# design.net
KiCad netlist of a schematic drawn in Altium Designer
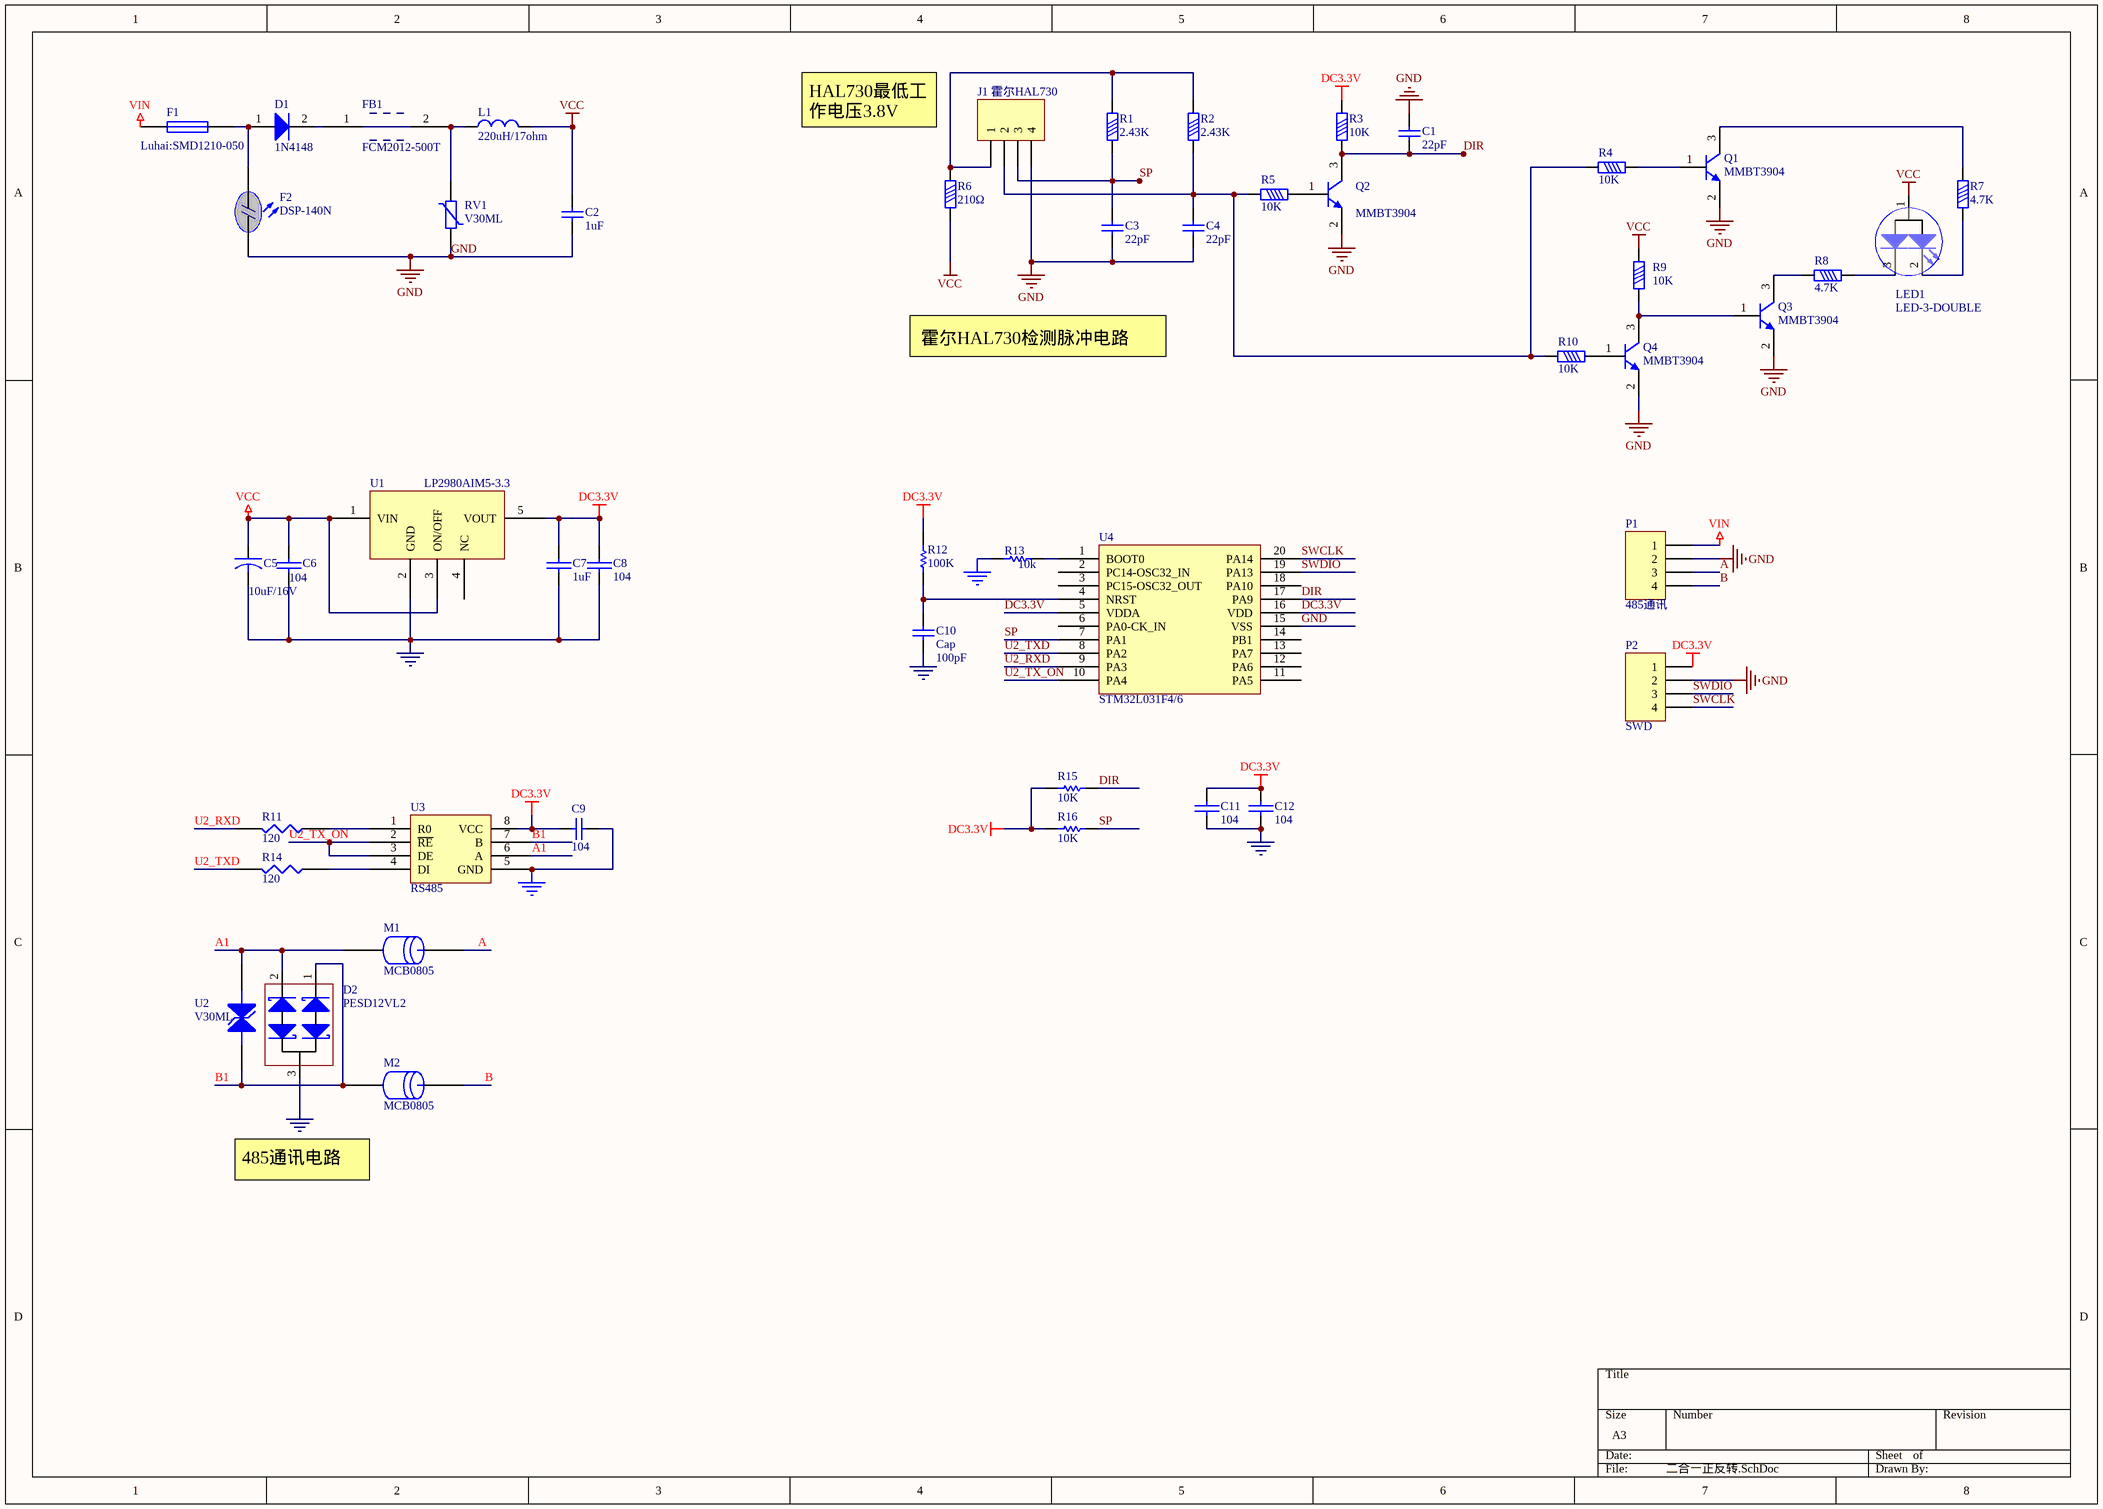
[diagram p0: 二合一正反转.SchDoc]

(export (version "E")
  (design (tool "Eeschema 10.0.6"))
  (components
    (comp (ref "C1")
      (value "22pF")
      (footprint "0603C")
      (description "Polarized Capacitor (Radial)")
      (fields (field (name "Comment") "Cap Chip 0603") (field (name "PUBLISHER") "Altium Limited"))
      (libsource (lib "EButterflyIntegratedLibrary") (part "Cap Chip 0603"))
    )
    (comp (ref "C2")
      (value "1uF")
      (footprint "0805C")
      (description "Polarized Capacitor (Radial)")
      (fields (field (name "PUBLISHER") "Altium Limited"))
      (libsource (lib "EButterflyIntegratedLibrary") (part "Cap Chip 0805"))
    )
    (comp (ref "C3")
      (value "22pF")
      (footprint "0603C")
      (description "Polarized Capacitor (Radial)")
      (fields (field (name "Comment") "Cap Chip 0603") (field (name "PUBLISHER") "Altium Limited"))
      (libsource (lib "EButterflyIntegratedLibrary") (part "Cap Chip 0603"))
    )
    (comp (ref "C4")
      (value "22pF")
      (footprint "0603C")
      (description "Polarized Capacitor (Radial)")
      (fields (field (name "Comment") "Cap Chip 0603") (field (name "PUBLISHER") "Altium Limited"))
      (libsource (lib "EButterflyIntegratedLibrary") (part "Cap Chip 0603"))
    )
    (comp (ref "C5")
      (value "10uF/16V")
      (footprint "A3216")
      (description "Capacitor")
      (libsource (lib "*") (part "CAPACITOR"))
    )
    (comp (ref "C6")
      (value "104")
      (footprint "0603C")
      (description "Capacitor")
      (libsource (lib "*") (part "CAP"))
    )
    (comp (ref "C7")
      (value "1uF")
      (footprint "0603C")
      (description "Capacitor")
      (libsource (lib "*") (part "CAP"))
    )
    (comp (ref "C8")
      (value "104")
      (footprint "0603C")
      (description "Capacitor")
      (libsource (lib "*") (part "CAP"))
    )
    (comp (ref "C9")
      (value "104")
      (footprint "0603C")
      (description "Capacitor")
      (fields (field (name "PUBLISHER") "*"))
      (libsource (lib "*") (part "Cap"))
    )
    (comp (ref "C10")
      (value "Cap")
      (footprint "0603C")
      (description "Capacitor")
      (fields (field (name "ALTIUM_VALUE") "100pF") (field (name "PUBLISHER") "Altium Limited"))
      (libsource (lib "Miscellaneous Devices") (part "Cap"))
    )
    (comp (ref "C11")
      (value "104")
      (footprint "0603C")
      (description "Capacitor")
      (libsource (lib "*") (part "CAP"))
    )
    (comp (ref "C12")
      (value "104")
      (footprint "0603C")
      (description "Capacitor")
      (libsource (lib "*") (part "CAP"))
    )
    (comp (ref "D1")
      (value "1N4148")
      (footprint "1N4148")
      (libsource (lib "Integrated_Library1") (part "1N4148"))
    )
    (comp (ref "D2") (value "PESD12VL2") (footprint "SOT23") (libsource (lib "lewis lib") (part "TVS")))
    (comp (ref "F1")
      (value "Luhai:SMD1210-050")
      (footprint "1210R")
      (description "Fuse")
      (fields (field (name "PUBLISHER") "Altium Limited"))
      (libsource (lib "Miscellaneous Devices") (part "Fuse 1"))
    )
    (comp (ref "F2")
      (value "DSP-140N")
      (footprint "DSP")
      (libsource (lib "Integrated_Library1") (part "DSP-140N"))
    )
    (comp (ref "FB1")
      (value "FCM2012-500T")
      (footprint "FB")
      (libsource (lib "Integrated_Library1") (part "FCM2012-500T"))
    )
    (comp (ref "J1")
      (value "霍尔HAL730")
      (footprint "HDR1X4")
      (description "Header, 4-Pin")
      (fields (field (name "PUBLISHER") "Altium Limited"))
      (libsource (lib "EButterflyIntegratedLibrary") (part "Header 4"))
    )
    (comp (ref "L1")
      (value "220uH/17ohm")
      (footprint "220uH/17ohm")
      (libsource (lib "Integrated_Library1") (part "220uH/17ohm"))
    )
    (comp (ref "LED1")
      (value "LED-3-DOUBLE")
      (footprint "LED-R3-H5-DOUBLE")
      (libsource (lib "Integrated_Library1") (part "DOUB-LED"))
    )
    (comp (ref "M1")
      (value "MCB0805")
      (footprint "0805F")
      (description "magnetic bead")
      (libsource (lib "lewis lib") (part "MAGNETIC BEAD"))
    )
    (comp (ref "M2")
      (value "MCB0805")
      (footprint "0805F")
      (description "magnetic bead")
      (libsource (lib "lewis lib") (part "MAGNETIC BEAD"))
    )
    (comp (ref "P1")
      (value "485通讯")
      (footprint "HDR1X4")
      (description "Header, 4-Pin, Right Angle")
      (fields (field (name "PUBLISHER") "Altium Limited"))
      (libsource (lib "Miscellaneous Connectors") (part "Header 4H"))
    )
    (comp (ref "P2")
      (value "SWD")
      (footprint "MHDR1X4")
      (description "Header, 4-Pin")
      (fields (field (name "PUBLISHER") "Altium Limited"))
      (libsource (lib "Miscellaneous Connectors") (part "Header 4"))
    )
    (comp (ref "Q1")
      (value "MMBT3904")
      (footprint "MMBT3904")
      (libsource (lib "Integrated_Library1") (part "MMBT3904"))
    )
    (comp (ref "Q2")
      (value "MMBT3904")
      (footprint "MMBT3904")
      (libsource (lib "Integrated_Library1") (part "MMBT3904"))
    )
    (comp (ref "Q3")
      (value "MMBT3904")
      (footprint "MMBT3904")
      (libsource (lib "Integrated_Library1") (part "MMBT3904"))
    )
    (comp (ref "Q4")
      (value "MMBT3904")
      (footprint "MMBT3904")
      (libsource (lib "Integrated_Library1") (part "MMBT3904"))
    )
    (comp (ref "R1")
      (value "2.43K")
      (footprint "0603C")
      (description "Resistor")
      (fields (field (name "Comment") "Resistor Chip 0603") (field (name "PUBLISHER") "Altium Limited"))
      (libsource (lib "") (part "Resistor Chip 0603_2"))
    )
    (comp (ref "R2")
      (value "2.43K")
      (footprint "0603C")
      (description "Resistor")
      (fields (field (name "Comment") "Resistor Chip 0603") (field (name "PUBLISHER") "Altium Limited"))
      (libsource (lib "") (part "Resistor Chip 0603_2"))
    )
    (comp (ref "R3")
      (value "10K")
      (footprint "0603C")
      (description "Resistor")
      (fields (field (name "Comment") "Resistor Chip 0603") (field (name "PUBLISHER") "Altium Limited"))
      (libsource (lib "") (part "Resistor Chip 0603_2"))
    )
    (comp (ref "R4")
      (value "10K")
      (footprint "0603C")
      (description "Resistor")
      (fields (field (name "Comment") "Resistor Chip 0603") (field (name "PUBLISHER") "Altium Limited"))
      (libsource (lib "") (part "Resistor Chip 0603_1"))
    )
    (comp (ref "R5")
      (value "10K")
      (footprint "0603C")
      (description "Resistor")
      (fields (field (name "Comment") "Resistor Chip 0603") (field (name "PUBLISHER") "Altium Limited"))
      (libsource (lib "") (part "Resistor Chip 0603_1"))
    )
    (comp (ref "R6")
      (value "210Ω")
      (footprint "0603C")
      (description "Resistor")
      (fields (field (name "Comment") "Resistor Chip 0603") (field (name "PUBLISHER") "Altium Limited"))
      (libsource (lib "EButterflyIntegratedLibrary") (part "Resistor Chip 0603"))
    )
    (comp (ref "R7")
      (value "4.7K")
      (footprint "0603C")
      (description "Resistor")
      (fields (field (name "Comment") "Resistor Chip 0603") (field (name "PUBLISHER") "Altium Limited"))
      (libsource (lib "EButterflyIntegratedLibrary") (part "Resistor Chip 0603"))
    )
    (comp (ref "R8")
      (value "4.7K")
      (footprint "0603C")
      (description "Resistor")
      (fields (field (name "Comment") "Resistor Chip 0603") (field (name "PUBLISHER") "Altium Limited"))
      (libsource (lib "") (part "Resistor Chip 0603_1"))
    )
    (comp (ref "R9")
      (value "10K")
      (footprint "0603C")
      (description "Resistor")
      (fields (field (name "Comment") "Resistor Chip 0603") (field (name "PUBLISHER") "Altium Limited"))
      (libsource (lib "EButterflyIntegratedLibrary") (part "Resistor Chip 0603"))
    )
    (comp (ref "R10")
      (value "10K")
      (footprint "0603C")
      (description "Resistor")
      (fields (field (name "Comment") "Resistor Chip 0603") (field (name "PUBLISHER") "Altium Limited"))
      (libsource (lib "") (part "Resistor Chip 0603_1"))
    )
    (comp (ref "R11") (value "120") (footprint "0603R") (libsource (lib "*") (part "RES1")))
    (comp (ref "R12")
      (value "100K")
      (footprint "0603R")
      (description "Resistor")
      (fields (field (name "PUBLISHER") "Altium Limited"))
      (libsource (lib "Miscellaneous Devices") (part "Res1"))
    )
    (comp (ref "R13")
      (value "10k")
      (footprint "0603R")
      (description "Resistor")
      (fields (field (name "PUBLISHER") "Altium Limited"))
      (libsource (lib "Miscellaneous Devices") (part "Res1"))
    )
    (comp (ref "R14") (value "120") (footprint "0603R") (libsource (lib "*") (part "RES1")))
    (comp (ref "R15")
      (value "10K")
      (footprint "0603R")
      (description "Resistor")
      (fields (field (name "PUBLISHER") "Altium Limited"))
      (libsource (lib "Miscellaneous Devices") (part "Res1"))
    )
    (comp (ref "R16")
      (value "10K")
      (footprint "0603R")
      (description "Resistor")
      (fields (field (name "PUBLISHER") "Altium Limited"))
      (libsource (lib "Miscellaneous Devices") (part "Res1"))
    )
    (comp (ref "RV1") (value "V30ML") (footprint "RV") (libsource (lib "Integrated_Library1") (part "V30ML")))
    (comp (ref "U1")
      (value "LP2980AIM5-3.3")
      (footprint "SOT-23-5")
      (libsource (lib "lewis lib") (part "LP2980AIM5-3.3"))
    )
    (comp (ref "U2") (value "V30ML") (footprint "0805C-E") (libsource (lib "*") (part "V30ML")))
    (comp (ref "U3") (value "RS485") (footprint "SOP8") (libsource (lib "*") (part "RS485")))
    (comp (ref "U4")
      (value "STM32L031F4/6")
      (footprint "TSSOP20")
      (libsource (lib "lewis lib") (part "STM32L031F4/6"))
    )
  )
  (nets
    (net (code "1") (name "/A") (class "Default")
      (node (ref "M1") (pin "2") (pintype "passive"))
      (node (ref "P1") (pin "3") (pinfunction "3_3") (pintype "passive"))
    )
    (net (code "2") (name "/A1") (class "Default")
      (node (ref "D2") (pin "2") (pinfunction "2_2") (pintype "passive"))
      (node (ref "M1") (pin "1") (pintype "passive"))
      (node (ref "U2") (pin "2") (pinfunction "2_2") (pintype "passive"))
      (node (ref "U3") (pin "6") (pinfunction "A_6") (pintype "passive"))
    )
    (net (code "3") (name "/B") (class "Default")
      (node (ref "M2") (pin "2") (pintype "passive"))
      (node (ref "P1") (pin "4") (pinfunction "4_4") (pintype "passive"))
    )
    (net (code "4") (name "/B1") (class "Default")
      (node (ref "D2") (pin "1") (pinfunction "1_1") (pintype "passive"))
      (node (ref "M2") (pin "1") (pintype "passive"))
      (node (ref "U2") (pin "1") (pinfunction "1_1") (pintype "passive"))
      (node (ref "U3") (pin "7") (pinfunction "B_7") (pintype "passive"))
    )
    (net (code "5") (name "/DIR") (class "Default")
      (node (ref "C1") (pin "1") (pinfunction "1_1") (pintype "passive"))
      (node (ref "Q2") (pin "3") (pinfunction "C_3") (pintype "passive"))
      (node (ref "R15") (pin "1") (pinfunction "1_1") (pintype "passive"))
      (node (ref "R3") (pin "1") (pinfunction "1_1") (pintype "passive"))
      (node (ref "U4") (pin "17") (pinfunction "PA9_17") (pintype "passive"))
    )
    (net (code "6") (name "/SP") (class "Default")
      (node (ref "C3") (pin "2") (pinfunction "2_2") (pintype "passive"))
      (node (ref "J1") (pin "3") (pinfunction "3_3") (pintype "passive"))
      (node (ref "R1") (pin "1") (pinfunction "1_1") (pintype "passive"))
      (node (ref "R16") (pin "2") (pinfunction "2_2") (pintype "passive"))
      (node (ref "U4") (pin "7") (pinfunction "PA1_7") (pintype "passive"))
    )
    (net (code "7") (name "/SWCLK") (class "Default")
      (node (ref "P2") (pin "4") (pinfunction "4_4") (pintype "passive"))
      (node (ref "U4") (pin "20") (pinfunction "PA14_20") (pintype "passive"))
    )
    (net (code "8") (name "/SWDIO") (class "Default")
      (node (ref "P2") (pin "3") (pinfunction "3_3") (pintype "passive"))
      (node (ref "U4") (pin "19") (pinfunction "PA13_19") (pintype "passive"))
    )
    (net (code "9") (name "/U2_RXD") (class "Default")
      (node (ref "R11") (pin "2") (pinfunction "2_2") (pintype "passive"))
      (node (ref "U4") (pin "9") (pinfunction "PA3_9") (pintype "passive"))
    )
    (net (code "10") (name "/U2_TXD") (class "Default")
      (node (ref "R14") (pin "2") (pinfunction "2_2") (pintype "passive"))
      (node (ref "U4") (pin "8") (pinfunction "PA2_8") (pintype "passive"))
    )
    (net (code "11") (name "/U2_TX_ON") (class "Default")
      (node (ref "U3") (pin "2") (pinfunction "~{RE}_2") (pintype "passive"))
      (node (ref "U3") (pin "3") (pinfunction "DE_3") (pintype "passive"))
      (node (ref "U4") (pin "10") (pinfunction "PA4_10") (pintype "passive"))
    )
    (net (code "12") (name "DC3.3V") (class "Default")
      (node (ref "C11") (pin "1") (pinfunction "1_1") (pintype "passive"))
      (node (ref "C12") (pin "1") (pinfunction "1_1") (pintype "passive"))
      (node (ref "C7") (pin "1") (pinfunction "1_1") (pintype "passive"))
      (node (ref "C8") (pin "1") (pinfunction "1_1") (pintype "passive"))
      (node (ref "C9") (pin "1") (pinfunction "1_1") (pintype "passive"))
      (node (ref "P2") (pin "1") (pinfunction "1_1") (pintype "passive"))
      (node (ref "R12") (pin "1") (pinfunction "1_1") (pintype "passive"))
      (node (ref "R15") (pin "2") (pinfunction "2_2") (pintype "passive"))
      (node (ref "R16") (pin "1") (pinfunction "1_1") (pintype "passive"))
      (node (ref "R3") (pin "2") (pinfunction "2_2") (pintype "passive"))
      (node (ref "U1") (pin "5") (pinfunction "VOUT_5") (pintype "passive"))
      (node (ref "U3") (pin "8") (pinfunction "VCC_8") (pintype "passive"))
      (node (ref "U4") (pin "16") (pinfunction "VDD_16") (pintype "passive"))
      (node (ref "U4") (pin "5") (pinfunction "VDDA_5") (pintype "passive"))
    )
    (net (code "13") (name "GND") (class "Default")
      (node (ref "C1") (pin "2") (pinfunction "2_2") (pintype "passive"))
      (node (ref "C10") (pin "1") (pinfunction "1_1") (pintype "passive"))
      (node (ref "C11") (pin "2") (pinfunction "2_2") (pintype "passive"))
      (node (ref "C12") (pin "2") (pinfunction "2_2") (pintype "passive"))
      (node (ref "C2") (pin "1") (pinfunction "1_1") (pintype "passive"))
      (node (ref "C3") (pin "1") (pinfunction "1_1") (pintype "passive"))
      (node (ref "C4") (pin "1") (pinfunction "1_1") (pintype "passive"))
      (node (ref "C5") (pin "2") (pinfunction "2_2") (pintype "passive"))
      (node (ref "C6") (pin "2") (pinfunction "2_2") (pintype "passive"))
      (node (ref "C7") (pin "2") (pinfunction "2_2") (pintype "passive"))
      (node (ref "C8") (pin "2") (pinfunction "2_2") (pintype "passive"))
      (node (ref "C9") (pin "2") (pinfunction "2_2") (pintype "passive"))
      (node (ref "D2") (pin "3") (pinfunction "3_3") (pintype "passive"))
      (node (ref "F2") (pin "2") (pinfunction "2_2") (pintype "passive"))
      (node (ref "J1") (pin "4") (pinfunction "4_4") (pintype "passive"))
      (node (ref "P1") (pin "2") (pinfunction "2_2") (pintype "passive"))
      (node (ref "P2") (pin "2") (pinfunction "2_2") (pintype "passive"))
      (node (ref "Q1") (pin "2") (pinfunction "E_2") (pintype "passive"))
      (node (ref "Q2") (pin "2") (pinfunction "E_2") (pintype "passive"))
      (node (ref "Q3") (pin "2") (pinfunction "E_2") (pintype "passive"))
      (node (ref "Q4") (pin "2") (pinfunction "E_2") (pintype "passive"))
      (node (ref "R13") (pin "2") (pinfunction "2_2") (pintype "passive"))
      (node (ref "RV1") (pin "1") (pinfunction "1_1") (pintype "passive"))
      (node (ref "U1") (pin "2") (pinfunction "GND_2") (pintype "passive"))
      (node (ref "U3") (pin "5") (pinfunction "GND_5") (pintype "passive"))
      (node (ref "U4") (pin "15") (pinfunction "VSS_15") (pintype "passive"))
    )
    (net (code "14") (name "Net-(C4-Pad2)") (class "Default")
      (node (ref "C4") (pin "2") (pinfunction "2_2") (pintype "passive"))
      (node (ref "J1") (pin "2") (pinfunction "2_2") (pintype "passive"))
      (node (ref "R10") (pin "2") (pinfunction "2_2") (pintype "passive"))
      (node (ref "R2") (pin "1") (pinfunction "1_1") (pintype "passive"))
      (node (ref "R4") (pin "2") (pinfunction "2_2") (pintype "passive"))
      (node (ref "R5") (pin "2") (pinfunction "2_2") (pintype "passive"))
    )
    (net (code "15") (name "Net-(D1-A)") (class "Default")
      (node (ref "D1") (pin "1") (pinfunction "A_1") (pintype "passive"))
      (node (ref "F1") (pin "2") (pinfunction "2_2") (pintype "passive"))
      (node (ref "F2") (pin "1") (pinfunction "1_1") (pintype "passive"))
    )
    (net (code "16") (name "Net-(D1-K)") (class "Default")
      (node (ref "D1") (pin "2") (pinfunction "K_2") (pintype "passive"))
      (node (ref "FB1") (pin "1") (pinfunction "1_1") (pintype "passive"))
    )
    (net (code "17") (name "Net-(FB1-Pad2)") (class "Default")
      (node (ref "FB1") (pin "2") (pinfunction "2_2") (pintype "passive"))
      (node (ref "L1") (pin "1") (pinfunction "1_1") (pintype "passive"))
      (node (ref "RV1") (pin "2") (pinfunction "2_2") (pintype "passive"))
    )
    (net (code "18") (name "Net-(J1-Pad1)") (class "Default")
      (node (ref "J1") (pin "1") (pinfunction "1_1") (pintype "passive"))
      (node (ref "R1") (pin "2") (pinfunction "2_2") (pintype "passive"))
      (node (ref "R2") (pin "2") (pinfunction "2_2") (pintype "passive"))
      (node (ref "R6") (pin "1") (pinfunction "1_1") (pintype "passive"))
    )
    (net (code "19") (name "Net-(LED1-A-Pad2)") (class "Default")
      (node (ref "LED1") (pin "2") (pinfunction "A_2") (pintype "passive"))
      (node (ref "R7") (pin "2") (pinfunction "2_2") (pintype "passive"))
    )
    (net (code "20") (name "Net-(LED1-A-Pad3)") (class "Default")
      (node (ref "LED1") (pin "3") (pinfunction "A_3") (pintype "passive"))
      (node (ref "R8") (pin "1") (pinfunction "1_1") (pintype "passive"))
    )
    (net (code "21") (name "Net-(Q1-B)") (class "Default")
      (node (ref "Q1") (pin "1") (pinfunction "B_1") (pintype "passive"))
      (node (ref "R4") (pin "1") (pinfunction "1_1") (pintype "passive"))
    )
    (net (code "22") (name "Net-(Q1-C)") (class "Default")
      (node (ref "Q1") (pin "3") (pinfunction "C_3") (pintype "passive"))
      (node (ref "R7") (pin "1") (pinfunction "1_1") (pintype "passive"))
    )
    (net (code "23") (name "Net-(Q2-B)") (class "Default")
      (node (ref "Q2") (pin "1") (pinfunction "B_1") (pintype "passive"))
      (node (ref "R5") (pin "1") (pinfunction "1_1") (pintype "passive"))
    )
    (net (code "24") (name "Net-(Q3-B)") (class "Default")
      (node (ref "Q3") (pin "1") (pinfunction "B_1") (pintype "passive"))
      (node (ref "Q4") (pin "3") (pinfunction "C_3") (pintype "passive"))
      (node (ref "R9") (pin "2") (pinfunction "2_2") (pintype "passive"))
    )
    (net (code "25") (name "Net-(Q3-C)") (class "Default")
      (node (ref "Q3") (pin "3") (pinfunction "C_3") (pintype "passive"))
      (node (ref "R8") (pin "2") (pinfunction "2_2") (pintype "passive"))
    )
    (net (code "26") (name "Net-(Q4-B)") (class "Default")
      (node (ref "Q4") (pin "1") (pinfunction "B_1") (pintype "passive"))
      (node (ref "R10") (pin "1") (pinfunction "1_1") (pintype "passive"))
    )
    (net (code "27") (name "Net-(U3-DI)") (class "Default")
      (node (ref "R14") (pin "1") (pinfunction "1_1") (pintype "passive"))
      (node (ref "U3") (pin "4") (pinfunction "DI_4") (pintype "passive"))
    )
    (net (code "28") (name "Net-(U3-R0)") (class "Default")
      (node (ref "R11") (pin "1") (pinfunction "1_1") (pintype "passive"))
      (node (ref "U3") (pin "1") (pinfunction "R0_1") (pintype "passive"))
    )
    (net (code "29") (name "Net-(U4-BOOT0)") (class "Default")
      (node (ref "R13") (pin "1") (pinfunction "1_1") (pintype "passive"))
      (node (ref "U4") (pin "1") (pinfunction "BOOT0_1") (pintype "passive"))
    )
    (net (code "30") (name "Net-(U4-NRST)") (class "Default")
      (node (ref "C10") (pin "2") (pinfunction "2_2") (pintype "passive"))
      (node (ref "R12") (pin "2") (pinfunction "2_2") (pintype "passive"))
      (node (ref "U4") (pin "4") (pinfunction "NRST_4") (pintype "passive"))
    )
    (net (code "31") (name "VCC") (class "Default")
      (node (ref "C2") (pin "2") (pinfunction "2_2") (pintype "passive"))
      (node (ref "C5") (pin "1") (pinfunction "1_1") (pintype "passive"))
      (node (ref "C6") (pin "1") (pinfunction "1_1") (pintype "passive"))
      (node (ref "L1") (pin "2") (pinfunction "2_2") (pintype "passive"))
      (node (ref "LED1") (pin "1") (pinfunction "K_1") (pintype "passive"))
      (node (ref "R6") (pin "2") (pinfunction "2_2") (pintype "passive"))
      (node (ref "R9") (pin "1") (pinfunction "1_1") (pintype "passive"))
      (node (ref "U1") (pin "1") (pinfunction "VIN_1") (pintype "passive"))
      (node (ref "U1") (pin "3") (pinfunction "ON/OFF_3") (pintype "passive"))
    )
    (net (code "32") (name "VIN") (class "Default")
      (node (ref "F1") (pin "1") (pinfunction "1_1") (pintype "passive"))
      (node (ref "P1") (pin "1") (pinfunction "1_1") (pintype "passive"))
    )
    (net (code "33") (name "unconnected-(U1-NC-Pad4)") (class "Default")
      (node (ref "U1") (pin "4") (pinfunction "NC_4") (pintype "passive"))
    )
    (net (code "34") (name "unconnected-(U4-PA0-CK_IN-Pad6)") (class "Default")
      (node (ref "U4") (pin "6") (pinfunction "PA0-CK_IN_6") (pintype "passive"))
    )
    (net (code "35") (name "unconnected-(U4-PA5-Pad11)") (class "Default")
      (node (ref "U4") (pin "11") (pinfunction "PA5_11") (pintype "passive"))
    )
    (net (code "36") (name "unconnected-(U4-PA6-Pad12)") (class "Default")
      (node (ref "U4") (pin "12") (pinfunction "PA6_12") (pintype "passive"))
    )
    (net (code "37") (name "unconnected-(U4-PA7-Pad13)") (class "Default")
      (node (ref "U4") (pin "13") (pinfunction "PA7_13") (pintype "passive"))
    )
    (net (code "38") (name "unconnected-(U4-PA10-Pad18)") (class "Default")
      (node (ref "U4") (pin "18") (pinfunction "PA10_18") (pintype "passive"))
    )
    (net (code "39") (name "unconnected-(U4-PB1-Pad14)") (class "Default")
      (node (ref "U4") (pin "14") (pinfunction "PB1_14") (pintype "passive"))
    )
    (net (code "40") (name "unconnected-(U4-PC14-OSC32_IN-Pad2)") (class "Default")
      (node (ref "U4") (pin "2") (pinfunction "PC14-OSC32_IN_2") (pintype "passive"))
    )
    (net (code "41") (name "unconnected-(U4-PC15-OSC32_OUT-Pad3)") (class "Default")
      (node (ref "U4") (pin "3") (pinfunction "PC15-OSC32_OUT_3") (pintype "passive"))
    )
  )
)
